# ESP_LoRa_Battery.net
KiCad netlist of a schematic drawn in EAGLE
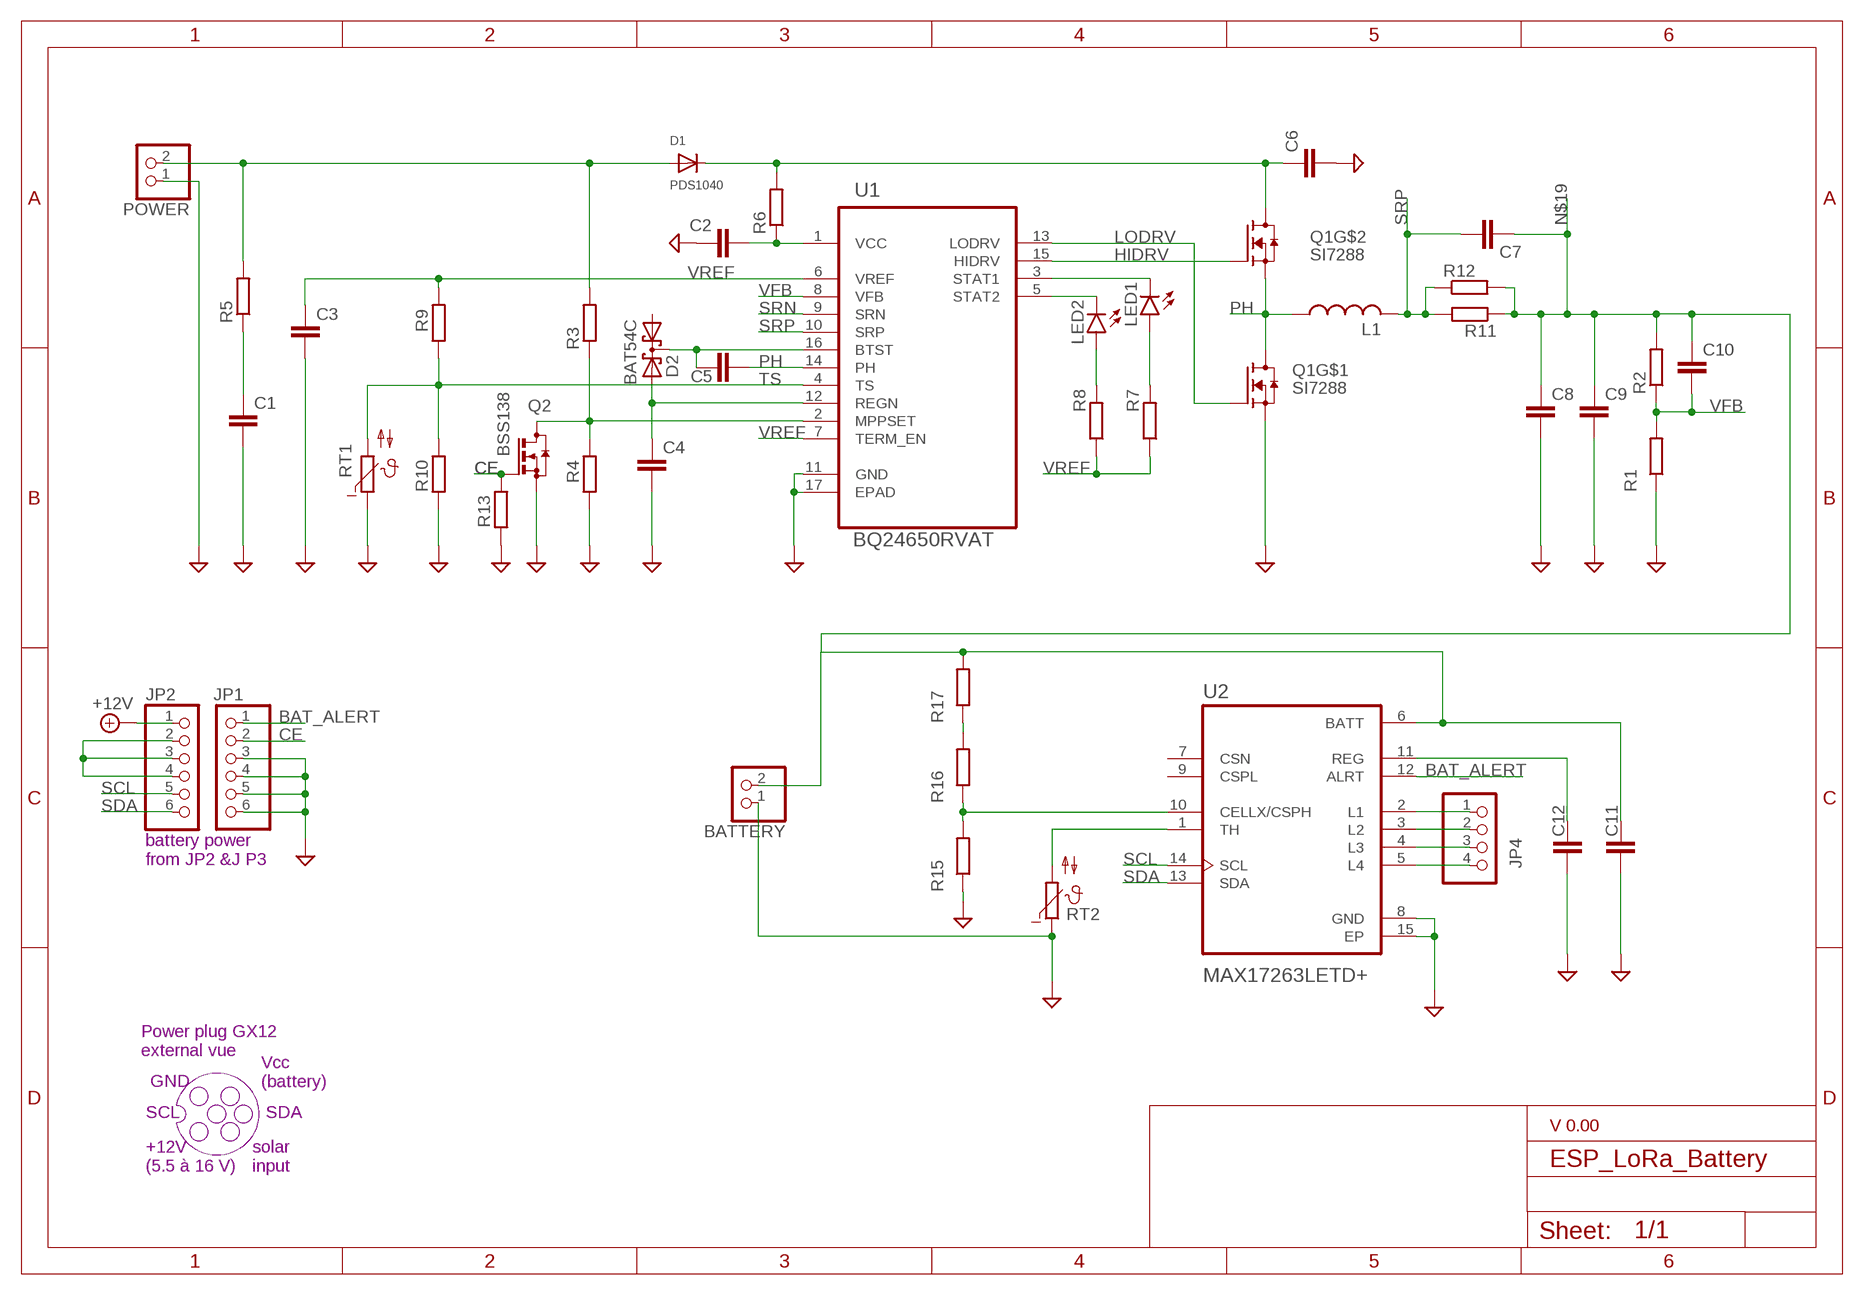
[diagram p0: schematic, sheet 1]

(export (version "E")
  (design (tool "Eeschema 10.0.6"))
  (components
    (comp (ref "BATTERY")
      (value "PINHD-1X2")
      (footprint "eagle-import:1X02")
      (libsource (lib "eagle-import") (part "PINHD-1X2"))
    )
    (comp (ref "C1")
      (value "C-EUC1206K")
      (footprint "eagle-import:C1206K")
      (libsource (lib "eagle-import") (part "C-EUC1206K"))
    )
    (comp (ref "C2")
      (value "C-EUC1206K")
      (footprint "eagle-import:C1206K")
      (libsource (lib "eagle-import") (part "C-EUC1206K"))
    )
    (comp (ref "C3")
      (value "C-EUC1206K")
      (footprint "eagle-import:C1206K")
      (libsource (lib "eagle-import") (part "C-EUC1206K"))
    )
    (comp (ref "C4")
      (value "C-EUC1206K")
      (footprint "eagle-import:C1206K")
      (libsource (lib "eagle-import") (part "C-EUC1206K"))
    )
    (comp (ref "C5")
      (value "C-EUC0805K")
      (footprint "eagle-import:C0805K")
      (libsource (lib "eagle-import") (part "C-EUC0805K"))
    )
    (comp (ref "C6")
      (value "C-EUC1206K")
      (footprint "eagle-import:C1206K")
      (libsource (lib "eagle-import") (part "C-EUC1206K"))
    )
    (comp (ref "C7")
      (value "C-EUC0805K")
      (footprint "eagle-import:C0805K")
      (libsource (lib "eagle-import") (part "C-EUC0805K"))
    )
    (comp (ref "C8")
      (value "C-EUC1206K")
      (footprint "eagle-import:C1206K")
      (libsource (lib "eagle-import") (part "C-EUC1206K"))
    )
    (comp (ref "C9")
      (value "C-EUC1206K")
      (footprint "eagle-import:C1206K")
      (libsource (lib "eagle-import") (part "C-EUC1206K"))
    )
    (comp (ref "C10")
      (value "C-EUC1206K")
      (footprint "eagle-import:C1206K")
      (libsource (lib "eagle-import") (part "C-EUC1206K"))
    )
    (comp (ref "C11")
      (value "C-EUC0805K")
      (footprint "eagle-import:C0805K")
      (libsource (lib "eagle-import") (part "C-EUC0805K"))
    )
    (comp (ref "C12")
      (value "C-EUC0805K")
      (footprint "eagle-import:C0805K")
      (libsource (lib "eagle-import") (part "C-EUC0805K"))
    )
    (comp (ref "D1")
      (value "PDS1040")
      (footprint "eagle-import:DIO_SBR10U200P5-13")
      (fields (field (name "DIGI-KEY_PART_NUMBER") "PDS1040LDICT-ND") (field (name "MF") "Diodes Inc."))
      (libsource (lib "eagle-import") (part "PDS1040"))
    )
    (comp (ref "D2")
      (value "BAT54C")
      (footprint "eagle-import:SOT23")
      (libsource (lib "eagle-import") (part "BAT54C"))
    )
    (comp (ref "JP1")
      (value "PINHD-1X6")
      (footprint "eagle-import:1X06")
      (libsource (lib "eagle-import") (part "PINHD-1X6"))
    )
    (comp (ref "JP2")
      (value "PINHD-1X6")
      (footprint "eagle-import:1X06")
      (libsource (lib "eagle-import") (part "PINHD-1X6"))
    )
    (comp (ref "JP4")
      (value "PINHD-1X4")
      (footprint "eagle-import:1X04")
      (libsource (lib "eagle-import") (part "PINHD-1X4"))
    )
    (comp (ref "L1")
      (value "L-USL2825P")
      (footprint "eagle-import:L2825P")
      (libsource (lib "eagle-import") (part "L-USL2825P"))
    )
    (comp (ref "LED1")
      (value "LEDSMT1206")
      (footprint "eagle-import:1206")
      (libsource (lib "eagle-import") (part "LEDSMT1206"))
    )
    (comp (ref "LED2")
      (value "LEDSMT1206")
      (footprint "eagle-import:1206")
      (libsource (lib "eagle-import") (part "LEDSMT1206"))
    )
    (comp (ref "POWER")
      (value "PINHD-1X2")
      (footprint "eagle-import:1X02")
      (libsource (lib "eagle-import") (part "PINHD-1X2"))
    )
    (comp (ref "Q1")
      (value "SI7288")
      (footprint "eagle-import:TRANS_SI7288DP-T1-GE3")
      (fields
        (field (name "DIGI-KEY_PART_NUMBER") "SI7288DP-T1-GE3CT-ND")
        (field (name "MF") "Vishay")
        (field (name "MP") "SI7288DP-T1-GE3")
      )
      (libsource (lib "eagle-import") (part "SI7288DP-T1-GE3"))
    )
    (comp (ref "Q2")
      (value "BSS138")
      (footprint "eagle-import:SOT23")
      (libsource (lib "eagle-import") (part "BSS138"))
    )
    (comp (ref "R1")
      (value "R-EU_R0805")
      (footprint "eagle-import:R0805")
      (libsource (lib "eagle-import") (part "R-EU_R0805"))
    )
    (comp (ref "R2")
      (value "R-EU_R0805")
      (footprint "eagle-import:R0805")
      (libsource (lib "eagle-import") (part "R-EU_R0805"))
    )
    (comp (ref "R3")
      (value "R-EU_R0805")
      (footprint "eagle-import:R0805")
      (libsource (lib "eagle-import") (part "R-EU_R0805"))
    )
    (comp (ref "R4")
      (value "R-EU_R0805")
      (footprint "eagle-import:R0805")
      (libsource (lib "eagle-import") (part "R-EU_R0805"))
    )
    (comp (ref "R5")
      (value "R-EU_R2512")
      (footprint "eagle-import:R2512")
      (libsource (lib "eagle-import") (part "R-EU_R2512"))
    )
    (comp (ref "R6")
      (value "R-EU_R1206")
      (footprint "eagle-import:R1206")
      (libsource (lib "eagle-import") (part "R-EU_R1206"))
    )
    (comp (ref "R7")
      (value "RR1206")
      (footprint "eagle-import:R1206")
      (libsource (lib "eagle-import") (part "RR1206"))
    )
    (comp (ref "R8")
      (value "RR1206")
      (footprint "eagle-import:R1206")
      (libsource (lib "eagle-import") (part "RR1206"))
    )
    (comp (ref "R9")
      (value "R-EU_R0805")
      (footprint "eagle-import:R0805")
      (libsource (lib "eagle-import") (part "R-EU_R0805"))
    )
    (comp (ref "R10")
      (value "R-EU_R0805")
      (footprint "eagle-import:R0805")
      (libsource (lib "eagle-import") (part "R-EU_R0805"))
    )
    (comp (ref "R11")
      (value "R-EU_R2512")
      (footprint "eagle-import:R2512")
      (libsource (lib "eagle-import") (part "R-EU_R2512"))
    )
    (comp (ref "R12")
      (value "R-EU_R2512")
      (footprint "eagle-import:R2512")
      (libsource (lib "eagle-import") (part "R-EU_R2512"))
    )
    (comp (ref "R13")
      (value "R-EU_R0805")
      (footprint "eagle-import:R0805")
      (libsource (lib "eagle-import") (part "R-EU_R0805"))
    )
    (comp (ref "R15")
      (value "R-EU_R0805")
      (footprint "eagle-import:R0805")
      (libsource (lib "eagle-import") (part "R-EU_R0805"))
    )
    (comp (ref "R16")
      (value "R-EU_R0805")
      (footprint "eagle-import:R0805")
      (libsource (lib "eagle-import") (part "R-EU_R0805"))
    )
    (comp (ref "R17")
      (value "R-EU_R0805")
      (footprint "eagle-import:R0805")
      (libsource (lib "eagle-import") (part "R-EU_R0805"))
    )
    (comp (ref "RT1")
      (value "NTC642-6")
      (footprint "eagle-import:P642")
      (libsource (lib "eagle-import") (part "NTC642-6"))
    )
    (comp (ref "RT2")
      (value "NTC642-6")
      (footprint "eagle-import:P642")
      (libsource (lib "eagle-import") (part "NTC642-6"))
    )
    (comp (ref "U1")
      (value "BQ24650RVAT")
      (footprint "eagle-import:QFN50P350X350X100-17N")
      (fields (field (name "MF") "Texas Instruments"))
      (libsource (lib "eagle-import") (part "BQ24650RVAT"))
    )
    (comp (ref "U2")
      (value "MAX17263LETD+")
      (footprint "eagle-import:SON40P300X300X80-15N")
      (fields (field (name "MF") "Maxim Integrated"))
      (libsource (lib "eagle-import") (part "MAX17263LETD+"))
    )
  )
  (nets
    (net (code "1") (name "+12V") (class "Default")
      (node (ref "JP2") (pin "1") (pinfunction "1_1") (pintype "passive"))
    )
    (net (code "2") (name "/BAT_ALERT") (class "Default")
      (node (ref "JP1") (pin "1") (pinfunction "1_1") (pintype "passive"))
      (node (ref "U2") (pin "12") (pinfunction "ALRT_12") (pintype "output"))
    )
    (net (code "3") (name "/CE") (class "Default")
      (node (ref "JP1") (pin "2") (pinfunction "2_2") (pintype "passive"))
      (node (ref "Q2") (pin "1") (pinfunction "G_1") (pintype "passive"))
      (node (ref "R13") (pin "2") (pinfunction "2_2") (pintype "passive"))
    )
    (net (code "4") (name "/HIDRV") (class "Default")
      (node (ref "Q1") (pin "4") (pinfunction "G2_4") (pintype "passive"))
      (node (ref "U1") (pin "15") (pinfunction "HIDRV_15") (pintype "output"))
    )
    (net (code "5") (name "/LODRV") (class "Default")
      (node (ref "Q1") (pin "2") (pinfunction "G1_2") (pintype "passive"))
      (node (ref "U1") (pin "13") (pinfunction "LODRV_13") (pintype "output"))
    )
    (net (code "6") (name "/N$19") (class "Default")
      (node (ref "BATTERY") (pin "2") (pinfunction "2_2") (pintype "passive"))
      (node (ref "C10") (pin "1") (pinfunction "1_1") (pintype "passive"))
      (node (ref "C11") (pin "1") (pinfunction "1_1") (pintype "passive"))
      (node (ref "C7") (pin "2") (pinfunction "2_2") (pintype "passive"))
      (node (ref "C8") (pin "1") (pinfunction "1_1") (pintype "passive"))
      (node (ref "C9") (pin "1") (pinfunction "1_1") (pintype "passive"))
      (node (ref "R11") (pin "1") (pinfunction "1_1") (pintype "passive"))
      (node (ref "R12") (pin "2") (pinfunction "2_2") (pintype "passive"))
      (node (ref "R17") (pin "2") (pinfunction "2_2") (pintype "passive"))
      (node (ref "R2") (pin "2") (pinfunction "2_2") (pintype "passive"))
      (node (ref "U2") (pin "6") (pinfunction "BATT_6") (pintype "power_in"))
    )
    (net (code "7") (name "/PH") (class "Default")
      (node (ref "C5") (pin "2") (pinfunction "2_2") (pintype "passive"))
      (node (ref "L1") (pin "1") (pinfunction "1_1") (pintype "passive"))
      (node (ref "Q1") (pin "3") (pinfunction "S2_3") (pintype "passive"))
      (node (ref "Q1") (pin "7") (pinfunction "D1_7") (pintype "passive"))
      (node (ref "Q1") (pin "8") (pinfunction "D1_8") (pintype "passive"))
      (node (ref "Q1") (pin "9") (pinfunction "D1_9") (pintype "passive"))
      (node (ref "U1") (pin "14") (pinfunction "PH_14") (pintype "power_in"))
    )
    (net (code "8") (name "/SCL") (class "Default")
      (node (ref "JP2") (pin "5") (pinfunction "5_5") (pintype "passive"))
      (node (ref "U2") (pin "14") (pinfunction "SCL_14") (pintype "input"))
    )
    (net (code "9") (name "/SDA") (class "Default")
      (node (ref "JP2") (pin "6") (pinfunction "6_6") (pintype "passive"))
      (node (ref "U2") (pin "13") (pinfunction "SDA_13") (pintype "bidirectional"))
    )
    (net (code "10") (name "/SRN") (class "Default")
      (node (ref "U1") (pin "9") (pinfunction "SRN_9") (pintype "input"))
    )
    (net (code "11") (name "/SRP") (class "Default")
      (node (ref "C7") (pin "1") (pinfunction "1_1") (pintype "passive"))
      (node (ref "L1") (pin "2") (pinfunction "2_2") (pintype "passive"))
      (node (ref "R11") (pin "2") (pinfunction "2_2") (pintype "passive"))
      (node (ref "R12") (pin "1") (pinfunction "1_1") (pintype "passive"))
      (node (ref "U1") (pin "10") (pinfunction "SRP_10") (pintype "input"))
    )
    (net (code "12") (name "/TS") (class "Default")
      (node (ref "R10") (pin "2") (pinfunction "2_2") (pintype "passive"))
      (node (ref "R9") (pin "1") (pinfunction "1_1") (pintype "passive"))
      (node (ref "RT1") (pin "2") (pinfunction "2_2") (pintype "passive"))
      (node (ref "U1") (pin "4") (pinfunction "TS_4") (pintype "input"))
    )
    (net (code "13") (name "/VFB") (class "Default")
      (node (ref "C10") (pin "2") (pinfunction "2_2") (pintype "passive"))
      (node (ref "R1") (pin "2") (pinfunction "2_2") (pintype "passive"))
      (node (ref "R2") (pin "1") (pinfunction "1_1") (pintype "passive"))
      (node (ref "U1") (pin "8") (pinfunction "VFB_8") (pintype "input"))
    )
    (net (code "14") (name "/VREF") (class "Default")
      (node (ref "C3") (pin "1") (pinfunction "1_1") (pintype "passive"))
      (node (ref "R7") (pin "1") (pinfunction "1_1") (pintype "passive"))
      (node (ref "R8") (pin "1") (pinfunction "1_1") (pintype "passive"))
      (node (ref "R9") (pin "2") (pinfunction "2_2") (pintype "passive"))
      (node (ref "U1") (pin "6") (pinfunction "VREF_6") (pintype "power_in"))
      (node (ref "U1") (pin "7") (pinfunction "TERM_EN_7") (pintype "input"))
    )
    (net (code "15") (name "GND") (class "Default")
      (node (ref "BATTERY") (pin "1") (pinfunction "1_1") (pintype "passive"))
      (node (ref "C1") (pin "2") (pinfunction "2_2") (pintype "passive"))
      (node (ref "C11") (pin "2") (pinfunction "2_2") (pintype "passive"))
      (node (ref "C12") (pin "2") (pinfunction "2_2") (pintype "passive"))
      (node (ref "C2") (pin "2") (pinfunction "2_2") (pintype "passive"))
      (node (ref "C3") (pin "2") (pinfunction "2_2") (pintype "passive"))
      (node (ref "C4") (pin "2") (pinfunction "2_2") (pintype "passive"))
      (node (ref "C6") (pin "2") (pinfunction "2_2") (pintype "passive"))
      (node (ref "C8") (pin "2") (pinfunction "2_2") (pintype "passive"))
      (node (ref "C9") (pin "2") (pinfunction "2_2") (pintype "passive"))
      (node (ref "JP1") (pin "3") (pinfunction "3_3") (pintype "passive"))
      (node (ref "JP1") (pin "4") (pinfunction "4_4") (pintype "passive"))
      (node (ref "JP1") (pin "5") (pinfunction "5_5") (pintype "passive"))
      (node (ref "JP1") (pin "6") (pinfunction "6_6") (pintype "passive"))
      (node (ref "POWER") (pin "1") (pinfunction "1_1") (pintype "passive"))
      (node (ref "Q1") (pin "1") (pinfunction "S1_1") (pintype "passive"))
      (node (ref "Q2") (pin "2") (pinfunction "S_2") (pintype "passive"))
      (node (ref "R1") (pin "1") (pinfunction "1_1") (pintype "passive"))
      (node (ref "R10") (pin "1") (pinfunction "1_1") (pintype "passive"))
      (node (ref "R13") (pin "1") (pinfunction "1_1") (pintype "passive"))
      (node (ref "R15") (pin "1") (pinfunction "1_1") (pintype "passive"))
      (node (ref "R4") (pin "1") (pinfunction "1_1") (pintype "passive"))
      (node (ref "RT1") (pin "1") (pinfunction "1_1") (pintype "passive"))
      (node (ref "RT2") (pin "1") (pinfunction "1_1") (pintype "passive"))
      (node (ref "U1") (pin "11") (pinfunction "GND_11") (pintype "passive"))
      (node (ref "U1") (pin "17") (pinfunction "EPAD_17") (pintype "passive"))
      (node (ref "U2") (pin "15") (pinfunction "EP_15") (pintype "power_in"))
      (node (ref "U2") (pin "8") (pinfunction "GND_8") (pintype "power_in"))
    )
    (net (code "16") (name "Net-(C1-Pad1)") (class "Default")
      (node (ref "C1") (pin "1") (pinfunction "1_1") (pintype "passive"))
      (node (ref "R5") (pin "1") (pinfunction "1_1") (pintype "passive"))
    )
    (net (code "17") (name "Net-(D1-A-Pad2)") (class "Default")
      (node (ref "D1") (pin "2") (pinfunction "A_2") (pintype "passive"))
      (node (ref "D1") (pin "3") (pinfunction "A_3") (pintype "passive"))
      (node (ref "POWER") (pin "2") (pinfunction "2_2") (pintype "passive"))
      (node (ref "R3") (pin "2") (pinfunction "2_2") (pintype "passive"))
      (node (ref "R5") (pin "2") (pinfunction "2_2") (pintype "passive"))
    )
    (net (code "18") (name "Net-(D1-C)") (class "Default")
      (node (ref "C6") (pin "1") (pinfunction "1_1") (pintype "passive"))
      (node (ref "D1") (pin "1") (pinfunction "C_1") (pintype "passive"))
      (node (ref "Q1") (pin "10") (pinfunction "D2_10") (pintype "passive"))
      (node (ref "Q1") (pin "5") (pinfunction "D2_5") (pintype "passive"))
      (node (ref "Q1") (pin "6") (pinfunction "D2_6") (pintype "passive"))
      (node (ref "R6") (pin "2") (pinfunction "2_2") (pintype "passive"))
    )
    (net (code "19") (name "Net-(D2-A2)") (class "Default")
      (node (ref "C4") (pin "1") (pinfunction "1_1") (pintype "passive"))
      (node (ref "D2") (pin "2") (pinfunction "A2_2") (pintype "passive"))
      (node (ref "U1") (pin "12") (pinfunction "REGN_12") (pintype "input"))
    )
    (net (code "20") (name "Net-(D2-K1K2)") (class "Default")
      (node (ref "C5") (pin "1") (pinfunction "1_1") (pintype "passive"))
      (node (ref "D2") (pin "3") (pinfunction "K1K2_3") (pintype "passive"))
      (node (ref "U1") (pin "16") (pinfunction "BTST_16") (pintype "power_in"))
    )
    (net (code "21") (name "Net-(JP2-Pad2)") (class "Default")
      (node (ref "JP2") (pin "2") (pinfunction "2_2") (pintype "passive"))
      (node (ref "JP2") (pin "3") (pinfunction "3_3") (pintype "passive"))
      (node (ref "JP2") (pin "4") (pinfunction "4_4") (pintype "passive"))
    )
    (net (code "22") (name "Net-(LED1-PadA)") (class "Default")
      (node (ref "LED1") (pin "A") (pinfunction "A_A") (pintype "passive"))
      (node (ref "R7") (pin "2") (pinfunction "2_2") (pintype "passive"))
    )
    (net (code "23") (name "Net-(LED2-PadA)") (class "Default")
      (node (ref "LED2") (pin "A") (pinfunction "A_A") (pintype "passive"))
      (node (ref "R8") (pin "2") (pinfunction "2_2") (pintype "passive"))
    )
    (net (code "24") (name "Net-(Q2-D)") (class "Default")
      (node (ref "Q2") (pin "3") (pinfunction "D_3") (pintype "passive"))
      (node (ref "R3") (pin "1") (pinfunction "1_1") (pintype "passive"))
      (node (ref "R4") (pin "2") (pinfunction "2_2") (pintype "passive"))
      (node (ref "U1") (pin "2") (pinfunction "MPPSET_2") (pintype "input"))
    )
    (net (code "25") (name "Net-(R16-Pad2)") (class "Default")
      (node (ref "R16") (pin "2") (pinfunction "2_2") (pintype "passive"))
      (node (ref "R17") (pin "1") (pinfunction "1_1") (pintype "passive"))
    )
    (net (code "26") (name "Net-(U1-STAT1)") (class "Default")
      (node (ref "LED1") (pin "C") (pinfunction "C_C") (pintype "passive"))
      (node (ref "U1") (pin "3") (pinfunction "STAT1_3") (pintype "output"))
    )
    (net (code "27") (name "Net-(U1-STAT2)") (class "Default")
      (node (ref "LED2") (pin "C") (pinfunction "C_C") (pintype "passive"))
      (node (ref "U1") (pin "5") (pinfunction "STAT2_5") (pintype "output"))
    )
    (net (code "28") (name "Net-(U1-VCC)") (class "Default")
      (node (ref "C2") (pin "1") (pinfunction "1_1") (pintype "passive"))
      (node (ref "R6") (pin "1") (pinfunction "1_1") (pintype "passive"))
      (node (ref "U1") (pin "1") (pinfunction "VCC_1") (pintype "power_in"))
    )
    (net (code "29") (name "Net-(U2-CELLX{slash}CSPH)") (class "Default")
      (node (ref "R15") (pin "2") (pinfunction "2_2") (pintype "passive"))
      (node (ref "R16") (pin "1") (pinfunction "1_1") (pintype "passive"))
      (node (ref "U2") (pin "10") (pinfunction "CELLX/CSPH_10") (pintype "input"))
    )
    (net (code "30") (name "Net-(U2-L1)") (class "Default")
      (node (ref "JP4") (pin "1") (pinfunction "1_1") (pintype "passive"))
      (node (ref "U2") (pin "2") (pinfunction "L1_2") (pintype "output"))
    )
    (net (code "31") (name "Net-(U2-L2)") (class "Default")
      (node (ref "JP4") (pin "2") (pinfunction "2_2") (pintype "passive"))
      (node (ref "U2") (pin "3") (pinfunction "L2_3") (pintype "output"))
    )
    (net (code "32") (name "Net-(U2-L3)") (class "Default")
      (node (ref "JP4") (pin "3") (pinfunction "3_3") (pintype "passive"))
      (node (ref "U2") (pin "4") (pinfunction "L3_4") (pintype "output"))
    )
    (net (code "33") (name "Net-(U2-L4)") (class "Default")
      (node (ref "JP4") (pin "4") (pinfunction "4_4") (pintype "passive"))
      (node (ref "U2") (pin "5") (pinfunction "L4_5") (pintype "output"))
    )
    (net (code "34") (name "Net-(U2-REG)") (class "Default")
      (node (ref "C12") (pin "1") (pinfunction "1_1") (pintype "passive"))
      (node (ref "U2") (pin "11") (pinfunction "REG_11") (pintype "output"))
    )
    (net (code "35") (name "Net-(U2-TH)") (class "Default")
      (node (ref "RT2") (pin "2") (pinfunction "2_2") (pintype "passive"))
      (node (ref "U2") (pin "1") (pinfunction "TH_1") (pintype "input"))
    )
    (net (code "36") (name "unconnected-(D2-A1-Pad1)") (class "Default")
      (node (ref "D2") (pin "1") (pinfunction "A1_1") (pintype "passive"))
    )
    (net (code "37") (name "unconnected-(U2-CSN-Pad7)") (class "Default")
      (node (ref "U2") (pin "7") (pinfunction "CSN_7") (pintype "input"))
    )
    (net (code "38") (name "unconnected-(U2-CSPL-Pad9)") (class "Default")
      (node (ref "U2") (pin "9") (pinfunction "CSPL_9") (pintype "input"))
    )
  )
)
